# ENERGIS_DispBrd_Rack-PDU_1_0_3.net
KiCad netlist of a schematic drawn in EAGLE
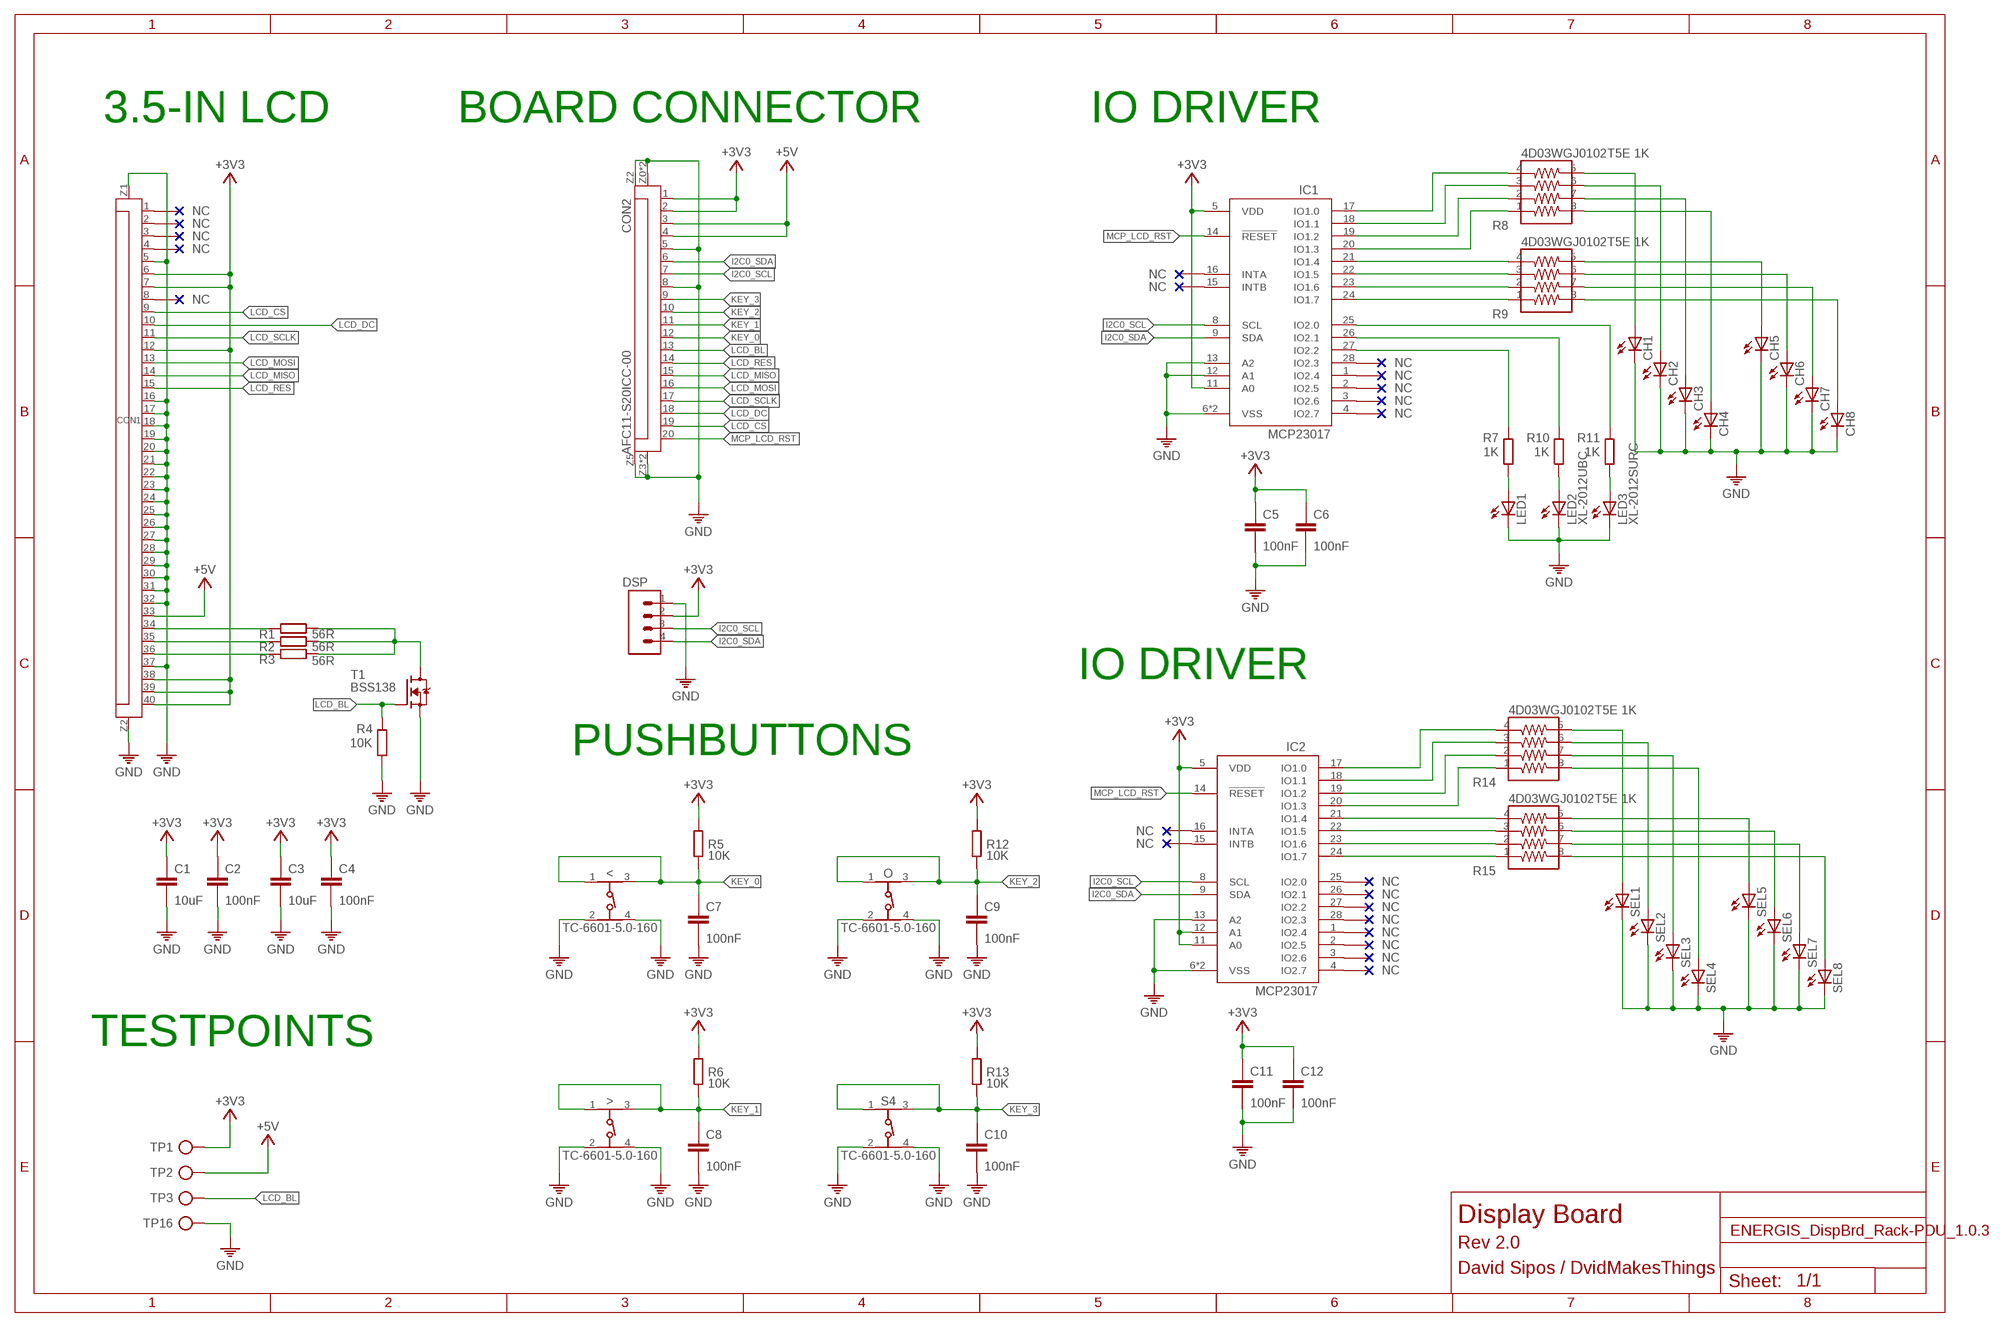
[diagram p0: schematic, sheet 1]

(export (version "E")
  (design (tool "Eeschema 10.0.6"))
  (components
    (comp (ref "<")
      (value "TC-6601-5.0-160")
      (footprint "eagle-import:430182043816")
      (libsource (lib "eagle-import") (part "430182043816"))
    )
    (comp (ref ">")
      (value "TC-6601-5.0-160")
      (footprint "eagle-import:430182043816")
      (libsource (lib "eagle-import") (part "430182043816"))
    )
    (comp (ref "C1")
      (value "10uF")
      (footprint "eagle-import:C0402")
      (libsource (lib "eagle-import") (part "C-0402"))
    )
    (comp (ref "C2")
      (value "100nF")
      (footprint "eagle-import:C0402")
      (libsource (lib "eagle-import") (part "C-0402"))
    )
    (comp (ref "C3")
      (value "10uF")
      (footprint "eagle-import:C0402")
      (libsource (lib "eagle-import") (part "C-0402"))
    )
    (comp (ref "C4")
      (value "100nF")
      (footprint "eagle-import:C0402")
      (libsource (lib "eagle-import") (part "C-0402"))
    )
    (comp (ref "C5")
      (value "100nF")
      (footprint "eagle-import:C0402")
      (libsource (lib "eagle-import") (part "C-0402"))
    )
    (comp (ref "C6")
      (value "100nF")
      (footprint "eagle-import:C0402")
      (libsource (lib "eagle-import") (part "C-0402"))
    )
    (comp (ref "C7")
      (value "100nF")
      (footprint "eagle-import:C0402")
      (libsource (lib "eagle-import") (part "C-0402"))
    )
    (comp (ref "C8")
      (value "100nF")
      (footprint "eagle-import:C0402")
      (libsource (lib "eagle-import") (part "C-0402"))
    )
    (comp (ref "C9")
      (value "100nF")
      (footprint "eagle-import:C0402")
      (libsource (lib "eagle-import") (part "C-0402"))
    )
    (comp (ref "C10")
      (value "100nF")
      (footprint "eagle-import:C0402")
      (libsource (lib "eagle-import") (part "C-0402"))
    )
    (comp (ref "C11")
      (value "100nF")
      (footprint "eagle-import:C0402")
      (libsource (lib "eagle-import") (part "C-0402"))
    )
    (comp (ref "C12")
      (value "100nF")
      (footprint "eagle-import:C0402")
      (libsource (lib "eagle-import") (part "C-0402"))
    )
    (comp (ref "CH1")
      (value "LEDCHIP-LED0805")
      (footprint "eagle-import:CHIP-LED0805")
      (libsource (lib "eagle-import") (part "LEDCHIP-LED0805"))
    )
    (comp (ref "CH2")
      (value "LEDCHIP-LED0805")
      (footprint "eagle-import:CHIP-LED0805")
      (libsource (lib "eagle-import") (part "LEDCHIP-LED0805"))
    )
    (comp (ref "CH3")
      (value "LEDCHIP-LED0805")
      (footprint "eagle-import:CHIP-LED0805")
      (libsource (lib "eagle-import") (part "LEDCHIP-LED0805"))
    )
    (comp (ref "CH4")
      (value "LEDCHIP-LED0805")
      (footprint "eagle-import:CHIP-LED0805")
      (libsource (lib "eagle-import") (part "LEDCHIP-LED0805"))
    )
    (comp (ref "CH5")
      (value "LEDCHIP-LED0805")
      (footprint "eagle-import:CHIP-LED0805")
      (libsource (lib "eagle-import") (part "LEDCHIP-LED0805"))
    )
    (comp (ref "CH6")
      (value "LEDCHIP-LED0805")
      (footprint "eagle-import:CHIP-LED0805")
      (libsource (lib "eagle-import") (part "LEDCHIP-LED0805"))
    )
    (comp (ref "CH7")
      (value "LEDCHIP-LED0805")
      (footprint "eagle-import:CHIP-LED0805")
      (libsource (lib "eagle-import") (part "LEDCHIP-LED0805"))
    )
    (comp (ref "CH8")
      (value "LEDCHIP-LED0805")
      (footprint "eagle-import:CHIP-LED0805")
      (libsource (lib "eagle-import") (part "LEDCHIP-LED0805"))
    )
    (comp (ref "CON1")
      (value "FPC40-HD")
      (footprint "eagle-import:FPC40_3.5TFT")
      (libsource (lib "eagle-import") (part "FPC40-HD"))
    )
    (comp (ref "CON2")
      (value "AFC11-S20ICC-00")
      (footprint "eagle-import:FPC20")
      (libsource (lib "eagle-import") (part "AFC11-S20ICC-00"))
    )
    (comp (ref "DSP")
      (value "CON-1X4")
      (footprint "eagle-import:1X4")
      (libsource (lib "eagle-import") (part "CON-1X4"))
    )
    (comp (ref "IC1")
      (value "MCP23017-E/ML")
      (footprint "eagle-import:QFN28[6X6]ML")
      (libsource (lib "eagle-import") (part "MCP23017-E/ML"))
    )
    (comp (ref "IC2")
      (value "MCP23017-E/ML")
      (footprint "eagle-import:QFN28[6X6]ML")
      (libsource (lib "eagle-import") (part "MCP23017-E/ML"))
    )
    (comp (ref "LED1")
      (value "LED3MM")
      (footprint "eagle-import:LED3MM")
      (libsource (lib "eagle-import") (part "LED3MM"))
    )
    (comp (ref "LED2")
      (value "XL-2012UBC")
      (footprint "eagle-import:LED3MM")
      (libsource (lib "eagle-import") (part "LED3MM"))
    )
    (comp (ref "LED3")
      (value "XL-2012SURC")
      (footprint "eagle-import:LED3MM")
      (libsource (lib "eagle-import") (part "LED3MM"))
    )
    (comp (ref "O")
      (value "TC-6601-5.0-160")
      (footprint "eagle-import:430182043816")
      (libsource (lib "eagle-import") (part "430182043816"))
    )
    (comp (ref "R1")
      (value "56R")
      (footprint "eagle-import:0402")
      (libsource (lib "eagle-import") (part "R0402"))
    )
    (comp (ref "R2")
      (value "56R")
      (footprint "eagle-import:0402")
      (libsource (lib "eagle-import") (part "R0402"))
    )
    (comp (ref "R3")
      (value "56R")
      (footprint "eagle-import:0402")
      (libsource (lib "eagle-import") (part "R0402"))
    )
    (comp (ref "R4")
      (value "10K")
      (footprint "eagle-import:0402")
      (libsource (lib "eagle-import") (part "R0402"))
    )
    (comp (ref "R5")
      (value "10K")
      (footprint "eagle-import:0402")
      (libsource (lib "eagle-import") (part "R0402"))
    )
    (comp (ref "R6")
      (value "10K")
      (footprint "eagle-import:0402")
      (libsource (lib "eagle-import") (part "R0402"))
    )
    (comp (ref "R7")
      (value "1K")
      (footprint "eagle-import:0402")
      (libsource (lib "eagle-import") (part "R0402"))
    )
    (comp (ref "R8")
      (value "4D03WGJ0102T5E 1K")
      (footprint "eagle-import:742C083103JP")
      (fields
        (field (name "MANUFACTURER") "CTS Resistor Products")
        (field (name "MPN") "742C083103JP")
        (field (name "CREATED_BY") "PCBLayout.com")
      )
      (libsource (lib "eagle-import") (part "742C083103JP"))
    )
    (comp (ref "R9")
      (value "4D03WGJ0102T5E 1K")
      (footprint "eagle-import:742C083103JP")
      (fields
        (field (name "MANUFACTURER") "CTS Resistor Products")
        (field (name "MPN") "742C083103JP")
        (field (name "CREATED_BY") "PCBLayout.com")
      )
      (libsource (lib "eagle-import") (part "742C083103JP"))
    )
    (comp (ref "R10")
      (value "1K")
      (footprint "eagle-import:0402")
      (libsource (lib "eagle-import") (part "R0402"))
    )
    (comp (ref "R11")
      (value "1K")
      (footprint "eagle-import:0402")
      (libsource (lib "eagle-import") (part "R0402"))
    )
    (comp (ref "R12")
      (value "10K")
      (footprint "eagle-import:0402")
      (libsource (lib "eagle-import") (part "R0402"))
    )
    (comp (ref "R13")
      (value "10K")
      (footprint "eagle-import:0402")
      (libsource (lib "eagle-import") (part "R0402"))
    )
    (comp (ref "R14")
      (value "4D03WGJ0102T5E 1K")
      (footprint "eagle-import:742C083103JP")
      (fields
        (field (name "MANUFACTURER") "CTS Resistor Products")
        (field (name "MPN") "742C083103JP")
        (field (name "CREATED_BY") "PCBLayout.com")
      )
      (libsource (lib "eagle-import") (part "742C083103JP"))
    )
    (comp (ref "R15")
      (value "4D03WGJ0102T5E 1K")
      (footprint "eagle-import:742C083103JP")
      (fields
        (field (name "MANUFACTURER") "CTS Resistor Products")
        (field (name "MPN") "742C083103JP")
        (field (name "CREATED_BY") "PCBLayout.com")
      )
      (libsource (lib "eagle-import") (part "742C083103JP"))
    )
    (comp (ref "S4")
      (value "TC-6601-5.0-160")
      (footprint "eagle-import:430182043816")
      (libsource (lib "eagle-import") (part "430182043816"))
    )
    (comp (ref "SEL1")
      (value "LEDCHIP-LED0805")
      (footprint "eagle-import:CHIP-LED0805")
      (libsource (lib "eagle-import") (part "LEDCHIP-LED0805"))
    )
    (comp (ref "SEL2")
      (value "LEDCHIP-LED0805")
      (footprint "eagle-import:CHIP-LED0805")
      (libsource (lib "eagle-import") (part "LEDCHIP-LED0805"))
    )
    (comp (ref "SEL3")
      (value "LEDCHIP-LED0805")
      (footprint "eagle-import:CHIP-LED0805")
      (libsource (lib "eagle-import") (part "LEDCHIP-LED0805"))
    )
    (comp (ref "SEL4")
      (value "LEDCHIP-LED0805")
      (footprint "eagle-import:CHIP-LED0805")
      (libsource (lib "eagle-import") (part "LEDCHIP-LED0805"))
    )
    (comp (ref "SEL5")
      (value "LEDCHIP-LED0805")
      (footprint "eagle-import:CHIP-LED0805")
      (libsource (lib "eagle-import") (part "LEDCHIP-LED0805"))
    )
    (comp (ref "SEL6")
      (value "LEDCHIP-LED0805")
      (footprint "eagle-import:CHIP-LED0805")
      (libsource (lib "eagle-import") (part "LEDCHIP-LED0805"))
    )
    (comp (ref "SEL7")
      (value "LEDCHIP-LED0805")
      (footprint "eagle-import:CHIP-LED0805")
      (libsource (lib "eagle-import") (part "LEDCHIP-LED0805"))
    )
    (comp (ref "SEL8")
      (value "LEDCHIP-LED0805")
      (footprint "eagle-import:CHIP-LED0805")
      (libsource (lib "eagle-import") (part "LEDCHIP-LED0805"))
    )
    (comp (ref "T1")
      (value "BSS138")
      (footprint "eagle-import:SOT23")
      (libsource (lib "eagle-import") (part "BSS138"))
    )
    (comp (ref "TP1") (value "TP") (footprint "eagle-import:TP") (libsource (lib "eagle-import") (part "TP")))
    (comp (ref "TP2") (value "TP") (footprint "eagle-import:TP") (libsource (lib "eagle-import") (part "TP")))
    (comp (ref "TP3") (value "TP") (footprint "eagle-import:TP") (libsource (lib "eagle-import") (part "TP")))
    (comp (ref "TP16")
      (value "TP")
      (footprint "eagle-import:TP")
      (libsource (lib "eagle-import") (part "TP"))
    )
  )
  (nets
    (net (code "1") (name "+3V3") (class "Default")
      (node (ref "C1") (pin "1") (pinfunction "1_1") (pintype "passive"))
      (node (ref "C11") (pin "1") (pinfunction "1_1") (pintype "passive"))
      (node (ref "C12") (pin "1") (pinfunction "1_1") (pintype "passive"))
      (node (ref "C2") (pin "1") (pinfunction "1_1") (pintype "passive"))
      (node (ref "C3") (pin "1") (pinfunction "1_1") (pintype "passive"))
      (node (ref "C4") (pin "1") (pinfunction "1_1") (pintype "passive"))
      (node (ref "C5") (pin "1") (pinfunction "1_1") (pintype "passive"))
      (node (ref "C6") (pin "1") (pinfunction "1_1") (pintype "passive"))
      (node (ref "CON1") (pin "12") (pinfunction "12_12") (pintype "bidirectional"))
      (node (ref "CON1") (pin "38") (pinfunction "38_38") (pintype "bidirectional"))
      (node (ref "CON1") (pin "39") (pinfunction "39_39") (pintype "bidirectional"))
      (node (ref "CON1") (pin "40") (pinfunction "40_40") (pintype "bidirectional"))
      (node (ref "CON1") (pin "6") (pinfunction "6_6") (pintype "bidirectional"))
      (node (ref "CON1") (pin "7") (pinfunction "7_7") (pintype "bidirectional"))
      (node (ref "CON2") (pin "1") (pinfunction "1_1") (pintype "bidirectional"))
      (node (ref "CON2") (pin "2") (pinfunction "2_2") (pintype "bidirectional"))
      (node (ref "DSP") (pin "2") (pinfunction "P$2_2") (pintype "bidirectional"))
      (node (ref "IC1") (pin "11") (pinfunction "A0_11") (pintype "bidirectional"))
      (node (ref "IC1") (pin "5") (pinfunction "VDD_5") (pintype "bidirectional"))
      (node (ref "IC2") (pin "11") (pinfunction "A0_11") (pintype "bidirectional"))
      (node (ref "IC2") (pin "12") (pinfunction "A1_12") (pintype "bidirectional"))
      (node (ref "IC2") (pin "5") (pinfunction "VDD_5") (pintype "bidirectional"))
      (node (ref "R12") (pin "1") (pinfunction "1_1") (pintype "passive"))
      (node (ref "R13") (pin "1") (pinfunction "1_1") (pintype "passive"))
      (node (ref "R5") (pin "1") (pinfunction "1_1") (pintype "passive"))
      (node (ref "R6") (pin "1") (pinfunction "1_1") (pintype "passive"))
      (node (ref "TP1") (pin "TP") (pinfunction "P$1_TP") (pintype "bidirectional"))
    )
    (net (code "2") (name "+5V") (class "Default")
      (node (ref "CON1") (pin "33") (pinfunction "33_33") (pintype "bidirectional"))
      (node (ref "CON2") (pin "3") (pinfunction "3_3") (pintype "bidirectional"))
      (node (ref "CON2") (pin "4") (pinfunction "4_4") (pintype "bidirectional"))
      (node (ref "TP2") (pin "TP") (pinfunction "P$1_TP") (pintype "bidirectional"))
    )
    (net (code "3") (name "GND") (class "Default")
      (node (ref "<") (pin "2") (pinfunction "2_2") (pintype "passive"))
      (node (ref "<") (pin "4") (pinfunction "4_4") (pintype "passive"))
      (node (ref ">") (pin "2") (pinfunction "2_2") (pintype "passive"))
      (node (ref ">") (pin "4") (pinfunction "4_4") (pintype "passive"))
      (node (ref "C1") (pin "2") (pinfunction "2_2") (pintype "passive"))
      (node (ref "C10") (pin "2") (pinfunction "2_2") (pintype "passive"))
      (node (ref "C11") (pin "2") (pinfunction "2_2") (pintype "passive"))
      (node (ref "C12") (pin "2") (pinfunction "2_2") (pintype "passive"))
      (node (ref "C2") (pin "2") (pinfunction "2_2") (pintype "passive"))
      (node (ref "C3") (pin "2") (pinfunction "2_2") (pintype "passive"))
      (node (ref "C4") (pin "2") (pinfunction "2_2") (pintype "passive"))
      (node (ref "C5") (pin "2") (pinfunction "2_2") (pintype "passive"))
      (node (ref "C6") (pin "2") (pinfunction "2_2") (pintype "passive"))
      (node (ref "C7") (pin "2") (pinfunction "2_2") (pintype "passive"))
      (node (ref "C8") (pin "2") (pinfunction "2_2") (pintype "passive"))
      (node (ref "C9") (pin "2") (pinfunction "2_2") (pintype "passive"))
      (node (ref "CH1") (pin "C") (pinfunction "C_C") (pintype "passive"))
      (node (ref "CH2") (pin "C") (pinfunction "C_C") (pintype "passive"))
      (node (ref "CH3") (pin "C") (pinfunction "C_C") (pintype "passive"))
      (node (ref "CH4") (pin "C") (pinfunction "C_C") (pintype "passive"))
      (node (ref "CH5") (pin "C") (pinfunction "C_C") (pintype "passive"))
      (node (ref "CH6") (pin "C") (pinfunction "C_C") (pintype "passive"))
      (node (ref "CH7") (pin "C") (pinfunction "C_C") (pintype "passive"))
      (node (ref "CH8") (pin "C") (pinfunction "C_C") (pintype "passive"))
      (node (ref "CON1") (pin "16") (pinfunction "16_16") (pintype "bidirectional"))
      (node (ref "CON1") (pin "17") (pinfunction "17_17") (pintype "bidirectional"))
      (node (ref "CON1") (pin "18") (pinfunction "18_18") (pintype "bidirectional"))
      (node (ref "CON1") (pin "19") (pinfunction "19_19") (pintype "bidirectional"))
      (node (ref "CON1") (pin "20") (pinfunction "20_20") (pintype "bidirectional"))
      (node (ref "CON1") (pin "21") (pinfunction "21_21") (pintype "bidirectional"))
      (node (ref "CON1") (pin "22") (pinfunction "22_22") (pintype "bidirectional"))
      (node (ref "CON1") (pin "23") (pinfunction "23_23") (pintype "bidirectional"))
      (node (ref "CON1") (pin "24") (pinfunction "24_24") (pintype "bidirectional"))
      (node (ref "CON1") (pin "25") (pinfunction "25_25") (pintype "bidirectional"))
      (node (ref "CON1") (pin "26") (pinfunction "26_26") (pintype "bidirectional"))
      (node (ref "CON1") (pin "27") (pinfunction "27_27") (pintype "bidirectional"))
      (node (ref "CON1") (pin "28") (pinfunction "28_28") (pintype "bidirectional"))
      (node (ref "CON1") (pin "29") (pinfunction "29_29") (pintype "bidirectional"))
      (node (ref "CON1") (pin "30") (pinfunction "30_30") (pintype "bidirectional"))
      (node (ref "CON1") (pin "31") (pinfunction "31_31") (pintype "bidirectional"))
      (node (ref "CON1") (pin "32") (pinfunction "32_32") (pintype "bidirectional"))
      (node (ref "CON1") (pin "37") (pinfunction "37_37") (pintype "bidirectional"))
      (node (ref "CON1") (pin "5") (pinfunction "5_5") (pintype "bidirectional"))
      (node (ref "CON1") (pin "Z1") (pinfunction "Z1_Z1") (pintype "bidirectional"))
      (node (ref "CON1") (pin "Z2") (pinfunction "Z2_Z2") (pintype "bidirectional"))
      (node (ref "CON2") (pin "5") (pinfunction "5_5") (pintype "bidirectional"))
      (node (ref "CON2") (pin "8") (pinfunction "8_8") (pintype "bidirectional"))
      (node (ref "CON2") (pin "Z0") (pinfunction "Z1_Z0") (pintype "bidirectional"))
      (node (ref "CON2") (pin "Z1") (pinfunction "Z1_Z1") (pintype "bidirectional"))
      (node (ref "CON2") (pin "Z2") (pinfunction "Z2_Z2") (pintype "bidirectional"))
      (node (ref "CON2") (pin "Z3") (pinfunction "Z3_Z3") (pintype "bidirectional"))
      (node (ref "CON2") (pin "Z4") (pinfunction "Z3_Z4") (pintype "bidirectional"))
      (node (ref "CON2") (pin "Z5") (pinfunction "Z4_Z5") (pintype "bidirectional"))
      (node (ref "DSP") (pin "1") (pinfunction "P$1_1") (pintype "bidirectional"))
      (node (ref "IC1") (pin "12") (pinfunction "A1_12") (pintype "bidirectional"))
      (node (ref "IC1") (pin "13") (pinfunction "A2_13") (pintype "bidirectional"))
      (node (ref "IC1") (pin "6") (pinfunction "VSS_6") (pintype "bidirectional"))
      (node (ref "IC1") (pin "PAD") (pinfunction "VSS_PAD") (pintype "bidirectional"))
      (node (ref "IC2") (pin "13") (pinfunction "A2_13") (pintype "bidirectional"))
      (node (ref "IC2") (pin "6") (pinfunction "VSS_6") (pintype "bidirectional"))
      (node (ref "IC2") (pin "PAD") (pinfunction "VSS_PAD") (pintype "bidirectional"))
      (node (ref "LED1") (pin "K") (pinfunction "C_K") (pintype "passive"))
      (node (ref "LED2") (pin "K") (pinfunction "C_K") (pintype "passive"))
      (node (ref "LED3") (pin "K") (pinfunction "C_K") (pintype "passive"))
      (node (ref "O") (pin "2") (pinfunction "2_2") (pintype "passive"))
      (node (ref "O") (pin "4") (pinfunction "4_4") (pintype "passive"))
      (node (ref "R4") (pin "2") (pinfunction "2_2") (pintype "passive"))
      (node (ref "S4") (pin "2") (pinfunction "2_2") (pintype "passive"))
      (node (ref "S4") (pin "4") (pinfunction "4_4") (pintype "passive"))
      (node (ref "SEL1") (pin "C") (pinfunction "C_C") (pintype "passive"))
      (node (ref "SEL2") (pin "C") (pinfunction "C_C") (pintype "passive"))
      (node (ref "SEL3") (pin "C") (pinfunction "C_C") (pintype "passive"))
      (node (ref "SEL4") (pin "C") (pinfunction "C_C") (pintype "passive"))
      (node (ref "SEL5") (pin "C") (pinfunction "C_C") (pintype "passive"))
      (node (ref "SEL6") (pin "C") (pinfunction "C_C") (pintype "passive"))
      (node (ref "SEL7") (pin "C") (pinfunction "C_C") (pintype "passive"))
      (node (ref "SEL8") (pin "C") (pinfunction "C_C") (pintype "passive"))
      (node (ref "T1") (pin "2") (pinfunction "S_2") (pintype "passive"))
      (node (ref "TP16") (pin "TP") (pinfunction "P$1_TP") (pintype "bidirectional"))
    )
    (net (code "4") (name "I2C0_SCL") (class "Default")
      (node (ref "CON2") (pin "7") (pinfunction "7_7") (pintype "bidirectional"))
      (node (ref "DSP") (pin "3") (pinfunction "P$3_3") (pintype "bidirectional"))
      (node (ref "IC1") (pin "8") (pinfunction "SCL_8") (pintype "bidirectional"))
      (node (ref "IC2") (pin "8") (pinfunction "SCL_8") (pintype "bidirectional"))
    )
    (net (code "5") (name "I2C0_SDA") (class "Default")
      (node (ref "CON2") (pin "6") (pinfunction "6_6") (pintype "bidirectional"))
      (node (ref "DSP") (pin "4") (pinfunction "P$4_4") (pintype "bidirectional"))
      (node (ref "IC1") (pin "9") (pinfunction "SDA_9") (pintype "bidirectional"))
      (node (ref "IC2") (pin "9") (pinfunction "SDA_9") (pintype "bidirectional"))
    )
    (net (code "6") (name "KEY_0") (class "Default")
      (node (ref "<") (pin "1") (pinfunction "1_1") (pintype "passive"))
      (node (ref "<") (pin "3") (pinfunction "3_3") (pintype "passive"))
      (node (ref "C7") (pin "1") (pinfunction "1_1") (pintype "passive"))
      (node (ref "CON2") (pin "12") (pinfunction "12_12") (pintype "bidirectional"))
      (node (ref "R5") (pin "2") (pinfunction "2_2") (pintype "passive"))
    )
    (net (code "7") (name "KEY_1") (class "Default")
      (node (ref ">") (pin "1") (pinfunction "1_1") (pintype "passive"))
      (node (ref ">") (pin "3") (pinfunction "3_3") (pintype "passive"))
      (node (ref "C8") (pin "1") (pinfunction "1_1") (pintype "passive"))
      (node (ref "CON2") (pin "11") (pinfunction "11_11") (pintype "bidirectional"))
      (node (ref "R6") (pin "2") (pinfunction "2_2") (pintype "passive"))
    )
    (net (code "8") (name "KEY_2") (class "Default")
      (node (ref "C9") (pin "1") (pinfunction "1_1") (pintype "passive"))
      (node (ref "CON2") (pin "10") (pinfunction "10_10") (pintype "bidirectional"))
      (node (ref "O") (pin "1") (pinfunction "1_1") (pintype "passive"))
      (node (ref "O") (pin "3") (pinfunction "3_3") (pintype "passive"))
      (node (ref "R12") (pin "2") (pinfunction "2_2") (pintype "passive"))
    )
    (net (code "9") (name "KEY_3") (class "Default")
      (node (ref "C10") (pin "1") (pinfunction "1_1") (pintype "passive"))
      (node (ref "CON2") (pin "9") (pinfunction "9_9") (pintype "bidirectional"))
      (node (ref "R13") (pin "2") (pinfunction "2_2") (pintype "passive"))
      (node (ref "S4") (pin "1") (pinfunction "1_1") (pintype "passive"))
      (node (ref "S4") (pin "3") (pinfunction "3_3") (pintype "passive"))
    )
    (net (code "10") (name "LCD_BL") (class "Default")
      (node (ref "CON2") (pin "13") (pinfunction "13_13") (pintype "bidirectional"))
      (node (ref "R4") (pin "1") (pinfunction "1_1") (pintype "passive"))
      (node (ref "T1") (pin "1") (pinfunction "G_1") (pintype "passive"))
      (node (ref "TP3") (pin "TP") (pinfunction "P$1_TP") (pintype "bidirectional"))
    )
    (net (code "11") (name "LCD_CS") (class "Default")
      (node (ref "CON1") (pin "9") (pinfunction "9_9") (pintype "bidirectional"))
      (node (ref "CON2") (pin "19") (pinfunction "19_19") (pintype "bidirectional"))
    )
    (net (code "12") (name "LCD_DC") (class "Default")
      (node (ref "CON1") (pin "10") (pinfunction "10_10") (pintype "bidirectional"))
      (node (ref "CON2") (pin "18") (pinfunction "18_18") (pintype "bidirectional"))
    )
    (net (code "13") (name "LCD_MISO") (class "Default")
      (node (ref "CON1") (pin "14") (pinfunction "14_14") (pintype "bidirectional"))
      (node (ref "CON2") (pin "15") (pinfunction "15_15") (pintype "bidirectional"))
    )
    (net (code "14") (name "LCD_MOSI") (class "Default")
      (node (ref "CON1") (pin "13") (pinfunction "13_13") (pintype "bidirectional"))
      (node (ref "CON2") (pin "16") (pinfunction "16_16") (pintype "bidirectional"))
    )
    (net (code "15") (name "LCD_RES") (class "Default")
      (node (ref "CON1") (pin "15") (pinfunction "15_15") (pintype "bidirectional"))
      (node (ref "CON2") (pin "14") (pinfunction "14_14") (pintype "bidirectional"))
    )
    (net (code "16") (name "LCD_SCLK") (class "Default")
      (node (ref "CON1") (pin "11") (pinfunction "11_11") (pintype "bidirectional"))
      (node (ref "CON2") (pin "17") (pinfunction "17_17") (pintype "bidirectional"))
    )
    (net (code "17") (name "MCP_LCD_RST") (class "Default")
      (node (ref "CON2") (pin "20") (pinfunction "20_20") (pintype "bidirectional"))
      (node (ref "IC1") (pin "14") (pinfunction "~{RESET}_14") (pintype "bidirectional"))
      (node (ref "IC2") (pin "14") (pinfunction "~{RESET}_14") (pintype "bidirectional"))
    )
    (net (code "18") (name "Net-(CH1-PadA)") (class "Default")
      (node (ref "CH1") (pin "A") (pinfunction "A_A") (pintype "passive"))
      (node (ref "R8") (pin "5") (pinfunction "5_5") (pintype "passive"))
    )
    (net (code "19") (name "Net-(CH2-PadA)") (class "Default")
      (node (ref "CH2") (pin "A") (pinfunction "A_A") (pintype "passive"))
      (node (ref "R8") (pin "6") (pinfunction "6_6") (pintype "passive"))
    )
    (net (code "20") (name "Net-(CH3-PadA)") (class "Default")
      (node (ref "CH3") (pin "A") (pinfunction "A_A") (pintype "passive"))
      (node (ref "R8") (pin "7") (pinfunction "7_7") (pintype "passive"))
    )
    (net (code "21") (name "Net-(CH4-PadA)") (class "Default")
      (node (ref "CH4") (pin "A") (pinfunction "A_A") (pintype "passive"))
      (node (ref "R8") (pin "8") (pinfunction "8_8") (pintype "passive"))
    )
    (net (code "22") (name "Net-(CH5-PadA)") (class "Default")
      (node (ref "CH5") (pin "A") (pinfunction "A_A") (pintype "passive"))
      (node (ref "R9") (pin "5") (pinfunction "5_5") (pintype "passive"))
    )
    (net (code "23") (name "Net-(CH6-PadA)") (class "Default")
      (node (ref "CH6") (pin "A") (pinfunction "A_A") (pintype "passive"))
      (node (ref "R9") (pin "6") (pinfunction "6_6") (pintype "passive"))
    )
    (net (code "24") (name "Net-(CH7-PadA)") (class "Default")
      (node (ref "CH7") (pin "A") (pinfunction "A_A") (pintype "passive"))
      (node (ref "R9") (pin "7") (pinfunction "7_7") (pintype "passive"))
    )
    (net (code "25") (name "Net-(CH8-PadA)") (class "Default")
      (node (ref "CH8") (pin "A") (pinfunction "A_A") (pintype "passive"))
      (node (ref "R9") (pin "8") (pinfunction "8_8") (pintype "passive"))
    )
    (net (code "26") (name "Net-(CON1-Pad34)") (class "Default")
      (node (ref "CON1") (pin "34") (pinfunction "34_34") (pintype "bidirectional"))
      (node (ref "R1") (pin "2") (pinfunction "2_2") (pintype "passive"))
    )
    (net (code "27") (name "Net-(CON1-Pad35)") (class "Default")
      (node (ref "CON1") (pin "35") (pinfunction "35_35") (pintype "bidirectional"))
      (node (ref "R2") (pin "2") (pinfunction "2_2") (pintype "passive"))
    )
    (net (code "28") (name "Net-(CON1-Pad36)") (class "Default")
      (node (ref "CON1") (pin "36") (pinfunction "36_36") (pintype "bidirectional"))
      (node (ref "R3") (pin "2") (pinfunction "2_2") (pintype "passive"))
    )
    (net (code "29") (name "Net-(IC1-IO1.0)") (class "Default")
      (node (ref "IC1") (pin "17") (pinfunction "IO1.0_17") (pintype "bidirectional"))
      (node (ref "R8") (pin "4") (pinfunction "4_4") (pintype "passive"))
    )
    (net (code "30") (name "Net-(IC1-IO1.1)") (class "Default")
      (node (ref "IC1") (pin "18") (pinfunction "IO1.1_18") (pintype "bidirectional"))
      (node (ref "R8") (pin "3") (pinfunction "3_3") (pintype "passive"))
    )
    (net (code "31") (name "Net-(IC1-IO1.2)") (class "Default")
      (node (ref "IC1") (pin "19") (pinfunction "IO1.2_19") (pintype "bidirectional"))
      (node (ref "R8") (pin "2") (pinfunction "2_2") (pintype "passive"))
    )
    (net (code "32") (name "Net-(IC1-IO1.3)") (class "Default")
      (node (ref "IC1") (pin "20") (pinfunction "IO1.3_20") (pintype "bidirectional"))
      (node (ref "R8") (pin "1") (pinfunction "1_1") (pintype "passive"))
    )
    (net (code "33") (name "Net-(IC1-IO1.4)") (class "Default")
      (node (ref "IC1") (pin "21") (pinfunction "IO1.4_21") (pintype "bidirectional"))
      (node (ref "R9") (pin "4") (pinfunction "4_4") (pintype "passive"))
    )
    (net (code "34") (name "Net-(IC1-IO1.5)") (class "Default")
      (node (ref "IC1") (pin "22") (pinfunction "IO1.5_22") (pintype "bidirectional"))
      (node (ref "R9") (pin "3") (pinfunction "3_3") (pintype "passive"))
    )
    (net (code "35") (name "Net-(IC1-IO1.6)") (class "Default")
      (node (ref "IC1") (pin "23") (pinfunction "IO1.6_23") (pintype "bidirectional"))
      (node (ref "R9") (pin "2") (pinfunction "2_2") (pintype "passive"))
    )
    (net (code "36") (name "Net-(IC1-IO1.7)") (class "Default")
      (node (ref "IC1") (pin "24") (pinfunction "IO1.7_24") (pintype "bidirectional"))
      (node (ref "R9") (pin "1") (pinfunction "1_1") (pintype "passive"))
    )
    (net (code "37") (name "Net-(IC1-IO2.0)") (class "Default")
      (node (ref "IC1") (pin "25") (pinfunction "IO2.0_25") (pintype "bidirectional"))
      (node (ref "R11") (pin "1") (pinfunction "1_1") (pintype "passive"))
    )
    (net (code "38") (name "Net-(IC1-IO2.1)") (class "Default")
      (node (ref "IC1") (pin "26") (pinfunction "IO2.1_26") (pintype "bidirectional"))
      (node (ref "R10") (pin "1") (pinfunction "1_1") (pintype "passive"))
    )
    (net (code "39") (name "Net-(IC1-IO2.2)") (class "Default")
      (node (ref "IC1") (pin "27") (pinfunction "IO2.2_27") (pintype "bidirectional"))
      (node (ref "R7") (pin "1") (pinfunction "1_1") (pintype "passive"))
    )
    (net (code "40") (name "Net-(IC2-IO1.0)") (class "Default")
      (node (ref "IC2") (pin "17") (pinfunction "IO1.0_17") (pintype "bidirectional"))
      (node (ref "R14") (pin "4") (pinfunction "4_4") (pintype "passive"))
    )
    (net (code "41") (name "Net-(IC2-IO1.1)") (class "Default")
      (node (ref "IC2") (pin "18") (pinfunction "IO1.1_18") (pintype "bidirectional"))
      (node (ref "R14") (pin "3") (pinfunction "3_3") (pintype "passive"))
    )
    (net (code "42") (name "Net-(IC2-IO1.2)") (class "Default")
      (node (ref "IC2") (pin "19") (pinfunction "IO1.2_19") (pintype "bidirectional"))
      (node (ref "R14") (pin "2") (pinfunction "2_2") (pintype "passive"))
    )
    (net (code "43") (name "Net-(IC2-IO1.3)") (class "Default")
      (node (ref "IC2") (pin "20") (pinfunction "IO1.3_20") (pintype "bidirectional"))
      (node (ref "R14") (pin "1") (pinfunction "1_1") (pintype "passive"))
    )
    (net (code "44") (name "Net-(IC2-IO1.4)") (class "Default")
      (node (ref "IC2") (pin "21") (pinfunction "IO1.4_21") (pintype "bidirectional"))
      (node (ref "R15") (pin "4") (pinfunction "4_4") (pintype "passive"))
    )
    (net (code "45") (name "Net-(IC2-IO1.5)") (class "Default")
      (node (ref "IC2") (pin "22") (pinfunction "IO1.5_22") (pintype "bidirectional"))
      (node (ref "R15") (pin "3") (pinfunction "3_3") (pintype "passive"))
    )
    (net (code "46") (name "Net-(IC2-IO1.6)") (class "Default")
      (node (ref "IC2") (pin "23") (pinfunction "IO1.6_23") (pintype "bidirectional"))
      (node (ref "R15") (pin "2") (pinfunction "2_2") (pintype "passive"))
    )
    (net (code "47") (name "Net-(IC2-IO1.7)") (class "Default")
      (node (ref "IC2") (pin "24") (pinfunction "IO1.7_24") (pintype "bidirectional"))
      (node (ref "R15") (pin "1") (pinfunction "1_1") (pintype "passive"))
    )
    (net (code "48") (name "Net-(LED1-PadA)") (class "Default")
      (node (ref "LED1") (pin "A") (pinfunction "A_A") (pintype "passive"))
      (node (ref "R7") (pin "2") (pinfunction "2_2") (pintype "passive"))
    )
    (net (code "49") (name "Net-(LED2-PadA)") (class "Default")
      (node (ref "LED2") (pin "A") (pinfunction "A_A") (pintype "passive"))
      (node (ref "R10") (pin "2") (pinfunction "2_2") (pintype "passive"))
    )
    (net (code "50") (name "Net-(LED3-PadA)") (class "Default")
      (node (ref "LED3") (pin "A") (pinfunction "A_A") (pintype "passive"))
      (node (ref "R11") (pin "2") (pinfunction "2_2") (pintype "passive"))
    )
    (net (code "51") (name "Net-(R14-Pad5)") (class "Default")
      (node (ref "R14") (pin "5") (pinfunction "5_5") (pintype "passive"))
      (node (ref "SEL1") (pin "A") (pinfunction "A_A") (pintype "passive"))
    )
    (net (code "52") (name "Net-(R14-Pad6)") (class "Default")
      (node (ref "R14") (pin "6") (pinfunction "6_6") (pintype "passive"))
      (node (ref "SEL2") (pin "A") (pinfunction "A_A") (pintype "passive"))
    )
    (net (code "53") (name "Net-(R14-Pad7)") (class "Default")
      (node (ref "R14") (pin "7") (pinfunction "7_7") (pintype "passive"))
      (node (ref "SEL3") (pin "A") (pinfunction "A_A") (pintype "passive"))
    )
    (net (code "54") (name "Net-(R14-Pad8)") (class "Default")
      (node (ref "R14") (pin "8") (pinfunction "8_8") (pintype "passive"))
      (node (ref "SEL4") (pin "A") (pinfunction "A_A") (pintype "passive"))
    )
    (net (code "55") (name "Net-(R15-Pad5)") (class "Default")
      (node (ref "R15") (pin "5") (pinfunction "5_5") (pintype "passive"))
      (node (ref "SEL5") (pin "A") (pinfunction "A_A") (pintype "passive"))
    )
    (net (code "56") (name "Net-(R15-Pad6)") (class "Default")
      (node (ref "R15") (pin "6") (pinfunction "6_6") (pintype "passive"))
      (node (ref "SEL6") (pin "A") (pinfunction "A_A") (pintype "passive"))
    )
    (net (code "57") (name "Net-(R15-Pad7)") (class "Default")
      (node (ref "R15") (pin "7") (pinfunction "7_7") (pintype "passive"))
      (node (ref "SEL7") (pin "A") (pinfunction "A_A") (pintype "passive"))
    )
    (net (code "58") (name "Net-(R15-Pad8)") (class "Default")
      (node (ref "R15") (pin "8") (pinfunction "8_8") (pintype "passive"))
      (node (ref "SEL8") (pin "A") (pinfunction "A_A") (pintype "passive"))
    )
    (net (code "59") (name "Net-(T1-D)") (class "Default")
      (node (ref "R1") (pin "1") (pinfunction "1_1") (pintype "passive"))
      (node (ref "R2") (pin "1") (pinfunction "1_1") (pintype "passive"))
      (node (ref "R3") (pin "1") (pinfunction "1_1") (pintype "passive"))
      (node (ref "T1") (pin "3") (pinfunction "D_3") (pintype "passive"))
    )
    (net (code "60") (name "unconnected-(CON1-Pad1)") (class "Default")
      (node (ref "CON1") (pin "1") (pinfunction "1_1") (pintype "bidirectional"))
    )
    (net (code "61") (name "unconnected-(CON1-Pad2)") (class "Default")
      (node (ref "CON1") (pin "2") (pinfunction "2_2") (pintype "bidirectional"))
    )
    (net (code "62") (name "unconnected-(CON1-Pad3)") (class "Default")
      (node (ref "CON1") (pin "3") (pinfunction "3_3") (pintype "bidirectional"))
    )
    (net (code "63") (name "unconnected-(CON1-Pad4)") (class "Default")
      (node (ref "CON1") (pin "4") (pinfunction "4_4") (pintype "bidirectional"))
    )
    (net (code "64") (name "unconnected-(CON1-Pad8)") (class "Default")
      (node (ref "CON1") (pin "8") (pinfunction "8_8") (pintype "bidirectional"))
    )
    (net (code "65") (name "unconnected-(IC1-INTA-Pad16)") (class "Default")
      (node (ref "IC1") (pin "16") (pinfunction "INTA_16") (pintype "bidirectional"))
    )
    (net (code "66") (name "unconnected-(IC1-INTB-Pad15)") (class "Default")
      (node (ref "IC1") (pin "15") (pinfunction "INTB_15") (pintype "bidirectional"))
    )
    (net (code "67") (name "unconnected-(IC1-IO2.3-Pad28)") (class "Default")
      (node (ref "IC1") (pin "28") (pinfunction "IO2.3_28") (pintype "bidirectional"))
    )
    (net (code "68") (name "unconnected-(IC1-IO2.4-Pad1)") (class "Default")
      (node (ref "IC1") (pin "1") (pinfunction "IO2.4_1") (pintype "bidirectional"))
    )
    (net (code "69") (name "unconnected-(IC1-IO2.5-Pad2)") (class "Default")
      (node (ref "IC1") (pin "2") (pinfunction "IO2.5_2") (pintype "bidirectional"))
    )
    (net (code "70") (name "unconnected-(IC1-IO2.6-Pad3)") (class "Default")
      (node (ref "IC1") (pin "3") (pinfunction "IO2.6_3") (pintype "bidirectional"))
    )
    (net (code "71") (name "unconnected-(IC1-IO2.7-Pad4)") (class "Default")
      (node (ref "IC1") (pin "4") (pinfunction "IO2.7_4") (pintype "bidirectional"))
    )
    (net (code "72") (name "unconnected-(IC2-INTA-Pad16)") (class "Default")
      (node (ref "IC2") (pin "16") (pinfunction "INTA_16") (pintype "bidirectional"))
    )
    (net (code "73") (name "unconnected-(IC2-INTB-Pad15)") (class "Default")
      (node (ref "IC2") (pin "15") (pinfunction "INTB_15") (pintype "bidirectional"))
    )
    (net (code "74") (name "unconnected-(IC2-IO2.0-Pad25)") (class "Default")
      (node (ref "IC2") (pin "25") (pinfunction "IO2.0_25") (pintype "bidirectional"))
    )
    (net (code "75") (name "unconnected-(IC2-IO2.1-Pad26)") (class "Default")
      (node (ref "IC2") (pin "26") (pinfunction "IO2.1_26") (pintype "bidirectional"))
    )
    (net (code "76") (name "unconnected-(IC2-IO2.2-Pad27)") (class "Default")
      (node (ref "IC2") (pin "27") (pinfunction "IO2.2_27") (pintype "bidirectional"))
    )
    (net (code "77") (name "unconnected-(IC2-IO2.3-Pad28)") (class "Default")
      (node (ref "IC2") (pin "28") (pinfunction "IO2.3_28") (pintype "bidirectional"))
    )
    (net (code "78") (name "unconnected-(IC2-IO2.4-Pad1)") (class "Default")
      (node (ref "IC2") (pin "1") (pinfunction "IO2.4_1") (pintype "bidirectional"))
    )
    (net (code "79") (name "unconnected-(IC2-IO2.5-Pad2)") (class "Default")
      (node (ref "IC2") (pin "2") (pinfunction "IO2.5_2") (pintype "bidirectional"))
    )
    (net (code "80") (name "unconnected-(IC2-IO2.6-Pad3)") (class "Default")
      (node (ref "IC2") (pin "3") (pinfunction "IO2.6_3") (pintype "bidirectional"))
    )
    (net (code "81") (name "unconnected-(IC2-IO2.7-Pad4)") (class "Default")
      (node (ref "IC2") (pin "4") (pinfunction "IO2.7_4") (pintype "bidirectional"))
    )
  )
)
